# Schematic.net
KiCad netlist of a schematic drawn in Altium Designer
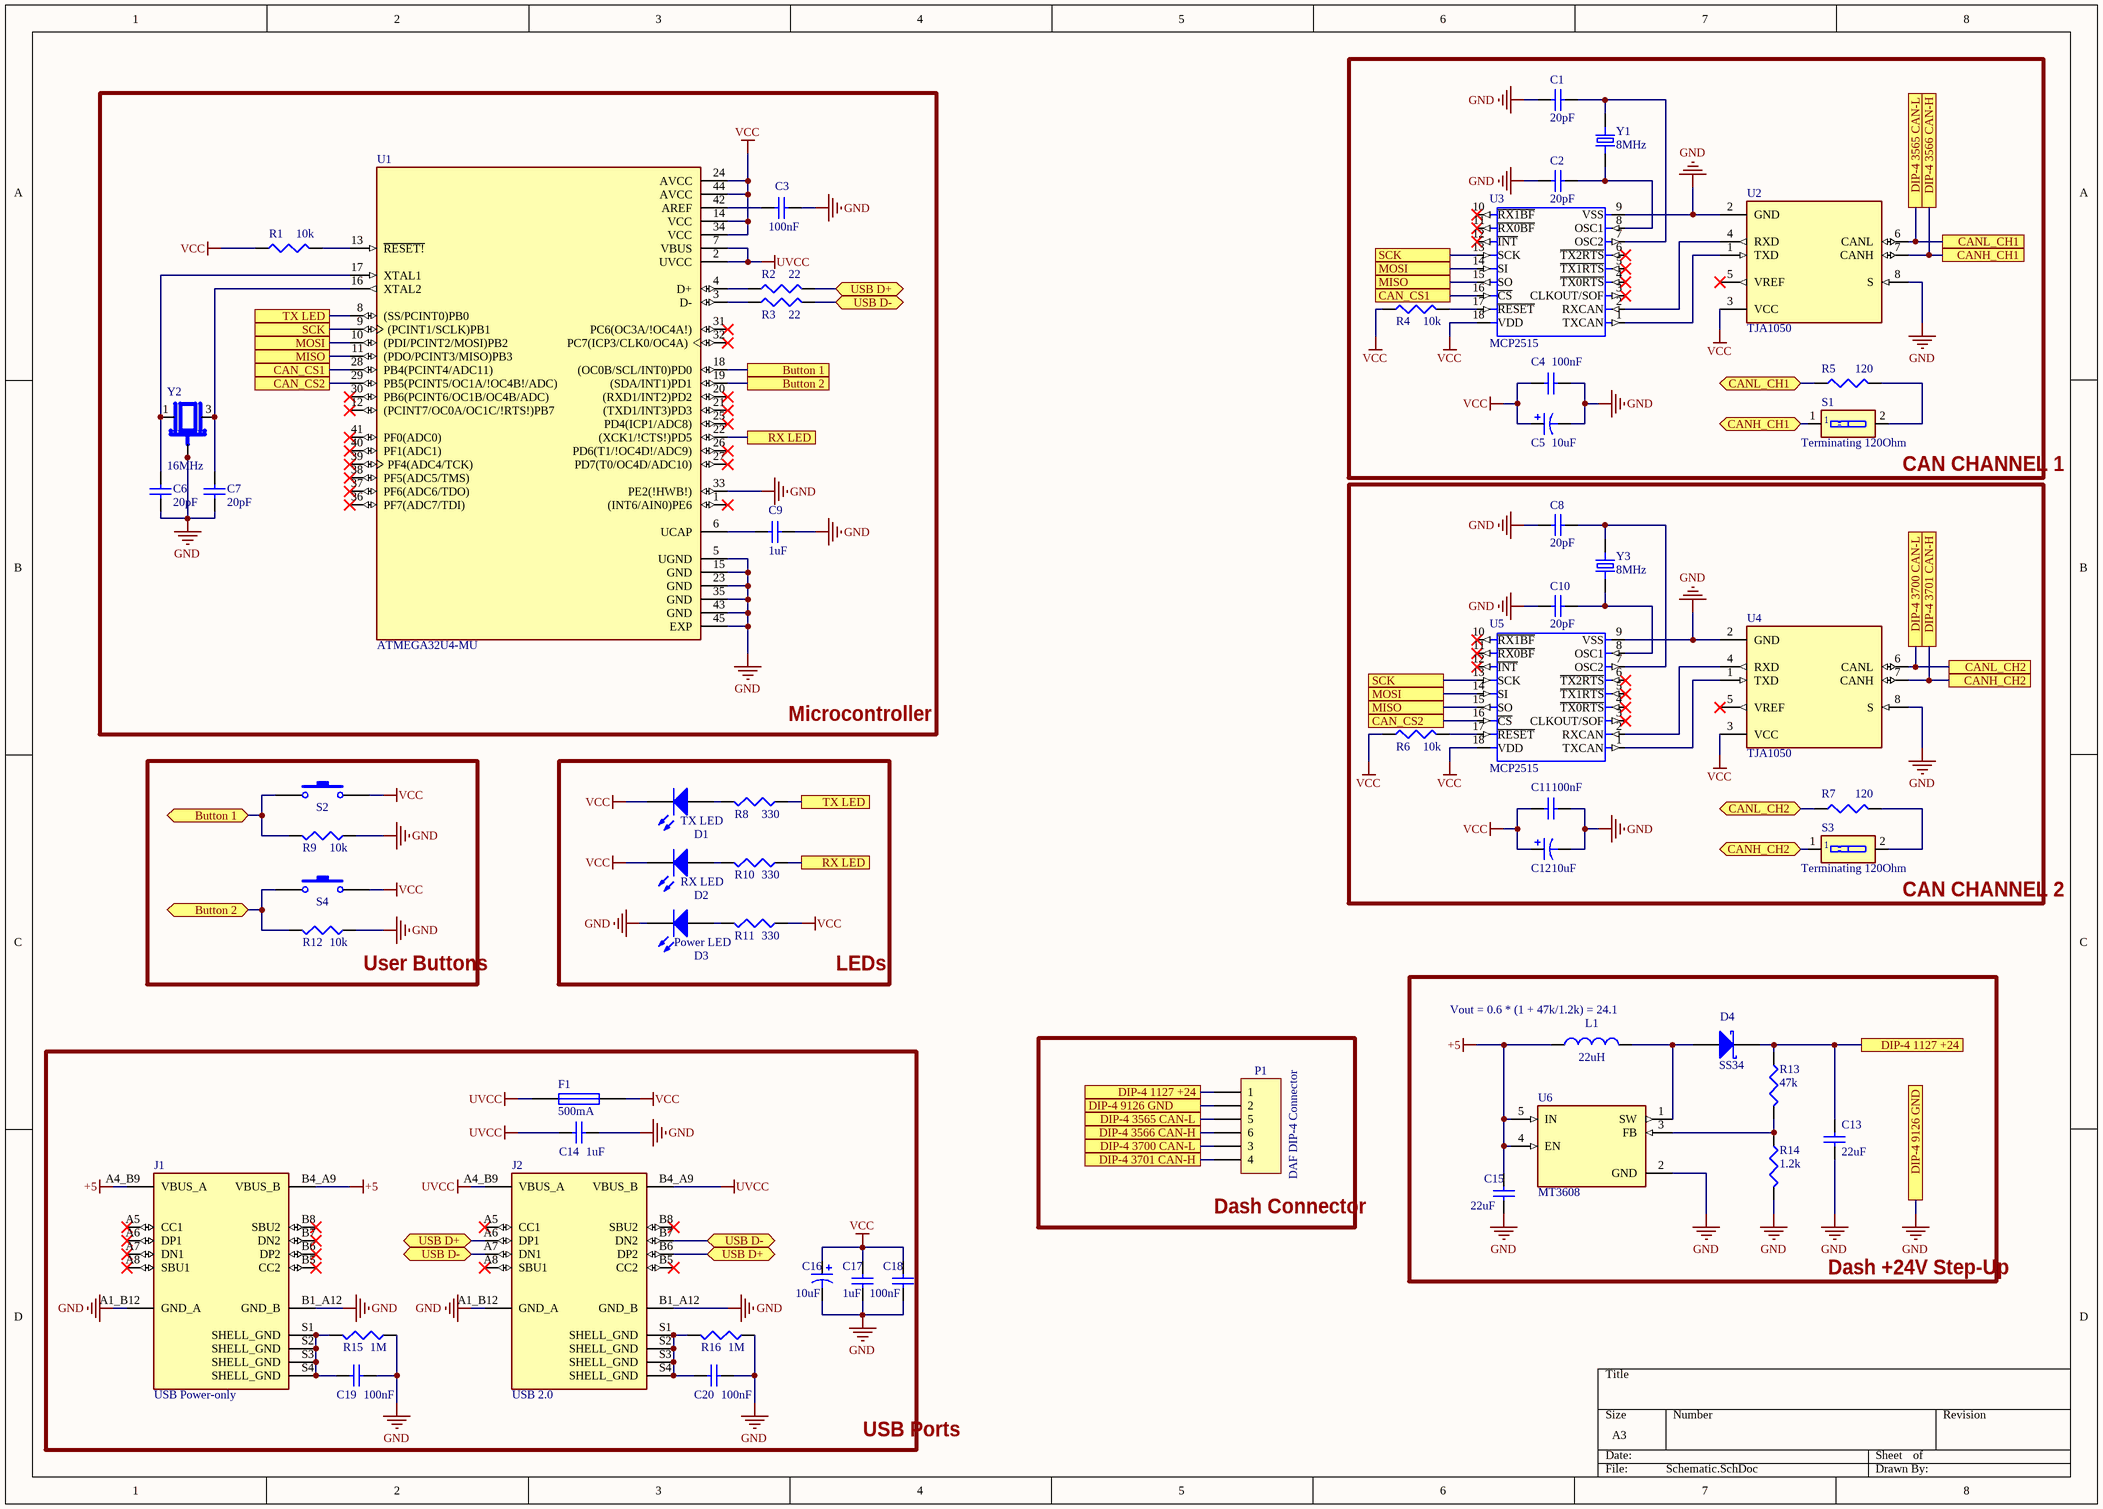
[diagram p0: Schematic.SchDoc]

(export (version "E")
  (design (tool "Eeschema 10.0.6"))
  (components
    (comp (ref "C1")
      (value "20pF")
      (footprint "C0805")
      (description "Capacitor")
      (fields (field (name "Comment") "Cap") (field (name "PUBLISHER") "Altium Limited"))
      (libsource (lib "Miscellaneous Devices") (part "Cap"))
    )
    (comp (ref "C2")
      (value "20pF")
      (footprint "C0805")
      (description "Capacitor")
      (fields (field (name "Comment") "Cap") (field (name "PUBLISHER") "Altium Limited"))
      (libsource (lib "Miscellaneous Devices") (part "Cap"))
    )
    (comp (ref "C3")
      (value "100nF")
      (footprint "C0805")
      (description "Capacitor")
      (fields (field (name "Comment") "Cap") (field (name "PUBLISHER") "Altium Limited"))
      (libsource (lib "Miscellaneous Devices") (part "Cap"))
    )
    (comp (ref "C4")
      (value "100nF")
      (footprint "C0805")
      (description "Capacitor")
      (fields (field (name "Comment") "Cap") (field (name "PUBLISHER") "Altium Limited"))
      (libsource (lib "Miscellaneous Devices") (part "Cap"))
    )
    (comp (ref "C5")
      (value "10uF")
      (footprint "C1206")
      (description "Polarized Capacitor (Surface Mount)")
      (fields (field (name "Comment") "Cap Pol3") (field (name "PUBLISHER") "Altium Limited"))
      (libsource (lib "Miscellaneous Devices") (part "Cap Pol3"))
    )
    (comp (ref "C6")
      (value "20pF")
      (footprint "C0805")
      (description "Capacitor")
      (fields (field (name "Comment") "Cap") (field (name "PUBLISHER") "Altium Limited"))
      (libsource (lib "Miscellaneous Devices") (part "Cap"))
    )
    (comp (ref "C7")
      (value "20pF")
      (footprint "C0805")
      (description "Capacitor")
      (fields (field (name "Comment") "Cap") (field (name "PUBLISHER") "Altium Limited"))
      (libsource (lib "Miscellaneous Devices") (part "Cap"))
    )
    (comp (ref "C8")
      (value "20pF")
      (footprint "C0805")
      (description "Capacitor")
      (fields (field (name "Comment") "Cap") (field (name "PUBLISHER") "Altium Limited"))
      (libsource (lib "Miscellaneous Devices") (part "Cap"))
    )
    (comp (ref "C9")
      (value "1uF")
      (footprint "C0805")
      (description "Capacitor")
      (fields (field (name "Comment") "Cap") (field (name "PUBLISHER") "Altium Limited"))
      (libsource (lib "Miscellaneous Devices") (part "Cap"))
    )
    (comp (ref "C10")
      (value "20pF")
      (footprint "C0805")
      (description "Capacitor")
      (fields (field (name "Comment") "Cap") (field (name "PUBLISHER") "Altium Limited"))
      (libsource (lib "Miscellaneous Devices") (part "Cap"))
    )
    (comp (ref "C11")
      (value "100nF")
      (footprint "C0805")
      (description "Capacitor")
      (fields (field (name "Comment") "Cap") (field (name "PUBLISHER") "Altium Limited"))
      (libsource (lib "Miscellaneous Devices") (part "Cap"))
    )
    (comp (ref "C12")
      (value "10uF")
      (footprint "C1206")
      (description "Polarized Capacitor (Surface Mount)")
      (fields (field (name "Comment") "Cap Pol3") (field (name "PUBLISHER") "Altium Limited"))
      (libsource (lib "Miscellaneous Devices") (part "Cap Pol3"))
    )
    (comp (ref "C13")
      (value "22uF")
      (footprint "C1206")
      (description "Capacitor")
      (fields (field (name "Comment") "Cap") (field (name "PUBLISHER") "Altium Limited"))
      (libsource (lib "Miscellaneous Devices") (part "Cap"))
    )
    (comp (ref "C14")
      (value "1uF")
      (footprint "C0805")
      (description "Capacitor")
      (fields (field (name "Comment") "Cap") (field (name "PUBLISHER") "Altium Limited"))
      (libsource (lib "Miscellaneous Devices") (part "Cap"))
    )
    (comp (ref "C15")
      (value "22uF")
      (footprint "C1206")
      (description "Capacitor")
      (fields (field (name "Comment") "Cap") (field (name "PUBLISHER") "Altium Limited"))
      (libsource (lib "Miscellaneous Devices") (part "Cap"))
    )
    (comp (ref "C16")
      (value "10uF")
      (footprint "C1206")
      (description "Polarized Capacitor (Surface Mount)")
      (fields (field (name "Comment") "Cap Pol3") (field (name "PUBLISHER") "Altium Limited"))
      (libsource (lib "Miscellaneous Devices") (part "Cap Pol3"))
    )
    (comp (ref "C17")
      (value "1uF")
      (footprint "C0805")
      (description "Capacitor")
      (fields (field (name "Comment") "Cap") (field (name "PUBLISHER") "Altium Limited"))
      (libsource (lib "Miscellaneous Devices") (part "Cap"))
    )
    (comp (ref "C18")
      (value "100nF")
      (footprint "C0805")
      (description "Capacitor")
      (fields (field (name "Comment") "Cap") (field (name "PUBLISHER") "Altium Limited"))
      (libsource (lib "Miscellaneous Devices") (part "Cap"))
    )
    (comp (ref "C19")
      (value "100nF")
      (footprint "C0805")
      (description "Capacitor")
      (fields (field (name "Comment") "Cap") (field (name "PUBLISHER") "Altium Limited"))
      (libsource (lib "Miscellaneous Devices") (part "Cap"))
    )
    (comp (ref "C20")
      (value "100nF")
      (footprint "C0805")
      (description "Capacitor")
      (fields (field (name "Comment") "Cap") (field (name "PUBLISHER") "Altium Limited"))
      (libsource (lib "Miscellaneous Devices") (part "Cap"))
    )
    (comp (ref "D1")
      (value "TX LED")
      (footprint "6-0805_L")
      (description "Typical RED GaAs LED")
      (fields (field (name "PUBLISHER") "Altium Limited"))
      (libsource (lib "Miscellaneous Devices") (part "LED1"))
    )
    (comp (ref "D2")
      (value "RX LED")
      (footprint "6-0805_L")
      (description "Typical RED GaAs LED")
      (fields (field (name "PUBLISHER") "Altium Limited"))
      (libsource (lib "Miscellaneous Devices") (part "LED1"))
    )
    (comp (ref "D3")
      (value "Power LED")
      (footprint "6-0805_L")
      (description "Typical RED GaAs LED")
      (fields (field (name "PUBLISHER") "Altium Limited"))
      (libsource (lib "Miscellaneous Devices") (part "LED1"))
    )
    (comp (ref "D4")
      (value "SS34")
      (footprint "SMC")
      (description "Schottky Diode")
      (fields (field (name "PUBLISHER") "Altium Limited"))
      (libsource (lib "Miscellaneous Devices") (part "D Schottky"))
    )
    (comp (ref "F1")
      (value "500mA")
      (footprint "C1206")
      (description "Fuse")
      (fields (field (name "PUBLISHER") "Altium Limited"))
      (libsource (lib "Miscellaneous Devices") (part "Fuse 1"))
    )
    (comp (ref "J1")
      (value "USB Power-only")
      (footprint "GCT_USB4505-03-0-A_REVA")
      (fields (field (name "MP") "USB4505-03-0-A") (field (name "MF") "Global Connector Technology"))
      (libsource (lib "Type-c") (part "USB4505-03-0-A_REVA"))
    )
    (comp (ref "J2")
      (value "USB 2.0")
      (footprint "GCT_USB4505-03-0-A_REVA")
      (fields (field (name "MP") "USB4505-03-0-A") (field (name "MF") "Global Connector Technology"))
      (libsource (lib "Type-c") (part "USB4505-03-0-A_REVA"))
    )
    (comp (ref "L1")
      (value "22uH")
      (footprint "IND_#B966BS-220M=P3")
      (description "Inductor")
      (fields (field (name "PUBLISHER") "Altium Limited"))
      (libsource (lib "Miscellaneous Devices") (part "Inductor"))
    )
    (comp (ref "P1")
      (value "DAF DIP-4 Connector")
      (footprint "HDR1X6")
      (description "Header, 6-Pin")
      (fields (field (name "PUBLISHER") "Altium Limited"))
      (libsource (lib "Miscellaneous Connectors") (part "Header 6"))
    )
    (comp (ref "R1")
      (value "10k")
      (footprint "6-0805_L")
      (description "Resistor")
      (fields (field (name "Comment") "Res3") (field (name "PUBLISHER") "Altium Limited"))
      (libsource (lib "Miscellaneous Devices") (part "Res3"))
    )
    (comp (ref "R2")
      (value "22")
      (footprint "J1-0603")
      (description "Resistor")
      (fields (field (name "Comment") "Res3") (field (name "PUBLISHER") "Altium Limited"))
      (libsource (lib "Miscellaneous Devices") (part "Res3"))
    )
    (comp (ref "R3")
      (value "22")
      (footprint "J1-0603")
      (description "Resistor")
      (fields (field (name "Comment") "Res3") (field (name "PUBLISHER") "Altium Limited"))
      (libsource (lib "Miscellaneous Devices") (part "Res3"))
    )
    (comp (ref "R4")
      (value "10k")
      (footprint "6-0805_L")
      (description "Resistor")
      (fields (field (name "Comment") "Res3") (field (name "PUBLISHER") "Altium Limited"))
      (libsource (lib "Miscellaneous Devices") (part "Res3"))
    )
    (comp (ref "R5")
      (value "120")
      (footprint "6-0805_L")
      (description "Resistor")
      (fields (field (name "Comment") "Res3") (field (name "PUBLISHER") "Altium Limited"))
      (libsource (lib "Miscellaneous Devices") (part "Res3"))
    )
    (comp (ref "R6")
      (value "10k")
      (footprint "6-0805_L")
      (description "Resistor")
      (fields (field (name "Comment") "Res3") (field (name "PUBLISHER") "Altium Limited"))
      (libsource (lib "Miscellaneous Devices") (part "Res3"))
    )
    (comp (ref "R7")
      (value "120")
      (footprint "6-0805_L")
      (description "Resistor")
      (fields (field (name "Comment") "Res3") (field (name "PUBLISHER") "Altium Limited"))
      (libsource (lib "Miscellaneous Devices") (part "Res3"))
    )
    (comp (ref "R8")
      (value "330")
      (footprint "6-0805_L")
      (description "Resistor")
      (fields (field (name "Comment") "Res3") (field (name "PUBLISHER") "Altium Limited"))
      (libsource (lib "Miscellaneous Devices") (part "Res3"))
    )
    (comp (ref "R9")
      (value "10k")
      (footprint "6-0805_L")
      (description "Resistor")
      (fields (field (name "Comment") "Res3") (field (name "PUBLISHER") "Altium Limited"))
      (libsource (lib "Miscellaneous Devices") (part "Res3"))
    )
    (comp (ref "R10")
      (value "330")
      (footprint "6-0805_L")
      (description "Resistor")
      (fields (field (name "Comment") "Res3") (field (name "PUBLISHER") "Altium Limited"))
      (libsource (lib "Miscellaneous Devices") (part "Res3"))
    )
    (comp (ref "R11")
      (value "330")
      (footprint "6-0805_L")
      (description "Resistor")
      (fields (field (name "Comment") "Res3") (field (name "PUBLISHER") "Altium Limited"))
      (libsource (lib "Miscellaneous Devices") (part "Res3"))
    )
    (comp (ref "R12")
      (value "10k")
      (footprint "6-0805_L")
      (description "Resistor")
      (fields (field (name "Comment") "Res3") (field (name "PUBLISHER") "Altium Limited"))
      (libsource (lib "Miscellaneous Devices") (part "Res3"))
    )
    (comp (ref "R13")
      (value "47k")
      (footprint "6-0805_L")
      (description "Resistor")
      (fields (field (name "Comment") "Res3") (field (name "PUBLISHER") "Altium Limited"))
      (libsource (lib "Miscellaneous Devices") (part "Res3"))
    )
    (comp (ref "R14")
      (value "1.2k")
      (footprint "6-0805_L")
      (description "Resistor")
      (fields (field (name "Comment") "Res3") (field (name "PUBLISHER") "Altium Limited"))
      (libsource (lib "Miscellaneous Devices") (part "Res3"))
    )
    (comp (ref "R15")
      (value "1M")
      (footprint "6-0805_L")
      (description "Resistor")
      (fields (field (name "Comment") "Res3") (field (name "PUBLISHER") "Altium Limited"))
      (libsource (lib "Miscellaneous Devices") (part "Res3"))
    )
    (comp (ref "R16")
      (value "1M")
      (footprint "6-0805_L")
      (description "Resistor")
      (fields (field (name "Comment") "Res3") (field (name "PUBLISHER") "Altium Limited"))
      (libsource (lib "Miscellaneous Devices") (part "Res3"))
    )
    (comp (ref "S1")
      (value "Terminating 120Ohm")
      (footprint "SW_5161390-1")
      (description "Switch DIP OFF ON SPST 1 Top Slide 25A 50VDC PC Pins 2.54mm Thru-Hole Box/Carton")
      (fields (field (name "MP") "5161390-1") (field (name "MF") "TE Connectivity"))
      (libsource (lib "DIP 1 switch") (part "5161390-1"))
    )
    (comp (ref "S2")
      (value "SW-PB")
      (footprint "SW_147873-2")
      (description "Switch")
      (fields (field (name "PUBLISHER") "Altium Limited"))
      (libsource (lib "Miscellaneous Devices") (part "SW-PB"))
    )
    (comp (ref "S3")
      (value "Terminating 120Ohm")
      (footprint "SW_5161390-1")
      (description "Switch DIP OFF ON SPST 1 Top Slide 25A 50VDC PC Pins 2.54mm Thru-Hole Box/Carton")
      (fields (field (name "MP") "5161390-1") (field (name "MF") "TE Connectivity"))
      (libsource (lib "DIP 1 switch") (part "5161390-1"))
    )
    (comp (ref "S4")
      (value "SW-PB")
      (footprint "SW_147873-2")
      (description "Switch")
      (fields (field (name "PUBLISHER") "Altium Limited"))
      (libsource (lib "Miscellaneous Devices") (part "SW-PB"))
    )
    (comp (ref "U1")
      (value "ATMEGA32U4-MU")
      (footprint "QFN50P700X700X100-45N")
      (description "AVR AVRÂ® ATmega Microcontroller IC 8-Bit 16MHz 32KB (16K x 16) FLASH 44-VQFN (7x7)")
      (fields (field (name "MF") "Microchip Technology / Atmel"))
      (libsource (lib "ATMEGA32U4-MU") (part "ATMEGA32U4-MU"))
    )
    (comp (ref "U2")
      (value "TJA1050")
      (footprint "SOIC127P600X175-8N")
      (description "1/1 Transceiver Half CANbus 8-SO")
      (fields (field (name "MF") "NXP USA") (field (name "MP") "TJA1050T/CM,118"))
      (libsource (lib "TJA1050T_CM_118") (part "TJA1050T/CM,118"))
    )
    (comp (ref "U3")
      (value "MCP2515")
      (footprint "SOIC18-1.27-11.5X7.5MM")
      (description "IC CAN CONTROLLER W/SPI 18SOIC")
      (fields (field (name "MF") "Microchip Technology") (field (name "MP") "MCP2515T-I/SO"))
      (libsource (lib "INTERFACE-MCP2515T-I_SO_SOIC18_") (part "INTERFACE-MCP2515T-I/SO(SOIC18)"))
    )
    (comp (ref "U4")
      (value "TJA1050")
      (footprint "SOIC127P600X175-8N")
      (description "1/1 Transceiver Half CANbus 8-SO")
      (fields (field (name "MF") "NXP USA") (field (name "MP") "TJA1050T/CM,118"))
      (libsource (lib "TJA1050T_CM_118") (part "TJA1050T/CM,118"))
    )
    (comp (ref "U5")
      (value "MCP2515")
      (footprint "SOIC18-1.27-11.5X7.5MM")
      (description "IC CAN CONTROLLER W/SPI 18SOIC")
      (fields (field (name "MF") "Microchip Technology") (field (name "MP") "MCP2515T-I/SO"))
      (libsource (lib "INTERFACE-MCP2515T-I_SO_SOIC18_") (part "INTERFACE-MCP2515T-I/SO(SOIC18)"))
    )
    (comp (ref "U6")
      (value "MT3608")
      (footprint "SOT95P280X145-6N")
      (description "High Efficiency 1.2MHz2A Step Up Converter")
      (fields (field (name "MF") "Aerosemi Technology Co., Ltd"))
      (libsource (lib "MT3608") (part "MT3608"))
    )
    (comp (ref "Y1")
      (value "8MHz")
      (footprint "XTAL_ECS-135-S-1")
      (fields (field (name "MP") "ECS-135-S-1"))
      (libsource (lib "quartz TH") (part "ECS-135-S-1"))
    )
    (comp (ref "Y2")
      (value "16MHz")
      (footprint "OSC_ABM3B-16.000MHZ-D-1-X-T")
      (description "16 MHz Â±10ppm Crystal 18pF 50 Ohms 4-SMD, No Lead")
      (fields (field (name "MP") "ABM3B-16.000MHZ-D-1-X-T") (field (name "MF") "ABRACON"))
      (libsource (lib "quartz") (part "ABM3B-16.000MHZ-D-1-X-T"))
    )
    (comp (ref "Y3")
      (value "8MHz")
      (footprint "XTAL_ECS-135-S-1")
      (fields (field (name "MP") "ECS-135-S-1"))
      (libsource (lib "quartz TH") (part "ECS-135-S-1"))
    )
  )
  (nets
    (net (code "1") (name "+5") (class "Default")
      (node (ref "C15") (pin "2") (pinfunction "2_2") (pintype "passive"))
      (node (ref "J1") (pin "A4_B9") (pinfunction "VBUS_A_A4_B9") (pintype "power_in"))
      (node (ref "J1") (pin "B4_A9") (pinfunction "VBUS_B_B4_A9") (pintype "power_in"))
      (node (ref "L1") (pin "1") (pinfunction "1_1") (pintype "passive"))
      (node (ref "U6") (pin "4") (pinfunction "EN_4") (pintype "input"))
      (node (ref "U6") (pin "5") (pinfunction "IN_5") (pintype "input"))
    )
    (net (code "2") (name "/Button 1") (class "Default")
      (node (ref "R9") (pin "2") (pinfunction "2_2") (pintype "passive"))
      (node (ref "S2") (pin "1") (pinfunction "1_1") (pintype "passive"))
      (node (ref "U1") (pin "18") (pinfunction "(OC0B/SCL/INT0)PD0_18") (pintype "bidirectional"))
    )
    (net (code "3") (name "/Button 2") (class "Default")
      (node (ref "R12") (pin "2") (pinfunction "2_2") (pintype "passive"))
      (node (ref "S4") (pin "1") (pinfunction "1_1") (pintype "passive"))
      (node (ref "U1") (pin "19") (pinfunction "(SDA/INT1)PD1_19") (pintype "bidirectional"))
    )
    (net (code "4") (name "/CANH_CH1") (class "Default")
      (node (ref "P1") (pin "6") (pinfunction "6_6") (pintype "passive"))
      (node (ref "S1") (pin "1") (pinfunction "1_1") (pintype "passive"))
      (node (ref "U2") (pin "7") (pinfunction "CANH_7") (pintype "bidirectional"))
    )
    (net (code "5") (name "/CANH_CH2") (class "Default")
      (node (ref "P1") (pin "4") (pinfunction "4_4") (pintype "passive"))
      (node (ref "S3") (pin "1") (pinfunction "1_1") (pintype "passive"))
      (node (ref "U4") (pin "7") (pinfunction "CANH_7") (pintype "bidirectional"))
    )
    (net (code "6") (name "/CANL_CH1") (class "Default")
      (node (ref "P1") (pin "5") (pinfunction "5_5") (pintype "passive"))
      (node (ref "R5") (pin "1") (pinfunction "1_1") (pintype "passive"))
      (node (ref "U2") (pin "6") (pinfunction "CANL_6") (pintype "bidirectional"))
    )
    (net (code "7") (name "/CANL_CH2") (class "Default")
      (node (ref "P1") (pin "3") (pinfunction "3_3") (pintype "passive"))
      (node (ref "R7") (pin "1") (pinfunction "1_1") (pintype "passive"))
      (node (ref "U4") (pin "6") (pinfunction "CANL_6") (pintype "bidirectional"))
    )
    (net (code "8") (name "/CAN_CS1") (class "Default")
      (node (ref "U1") (pin "28") (pinfunction "PB4(PCINT4/ADC11)_28") (pintype "bidirectional"))
      (node (ref "U3") (pin "16") (pinfunction "~{CS}_16") (pintype "input"))
    )
    (net (code "9") (name "/CAN_CS2") (class "Default")
      (node (ref "U1") (pin "29") (pinfunction "PB5(PCINT5/OC1A/!OC4B!/ADC)_29") (pintype "bidirectional"))
      (node (ref "U5") (pin "16") (pinfunction "~{CS}_16") (pintype "input"))
    )
    (net (code "10") (name "/DIP-4 1127 +24") (class "Default")
      (node (ref "C13") (pin "2") (pinfunction "2_2") (pintype "passive"))
      (node (ref "D4") (pin "2") (pinfunction "K_2") (pintype "passive"))
      (node (ref "P1") (pin "1") (pinfunction "1_1") (pintype "passive"))
      (node (ref "R13") (pin "1") (pinfunction "1_1") (pintype "passive"))
    )
    (net (code "11") (name "/MISO") (class "Default")
      (node (ref "U1") (pin "11") (pinfunction "(PDO/PCINT3/MISO)PB3_11") (pintype "bidirectional"))
      (node (ref "U3") (pin "15") (pinfunction "SO_15") (pintype "output"))
      (node (ref "U5") (pin "15") (pinfunction "SO_15") (pintype "output"))
    )
    (net (code "12") (name "/MOSI") (class "Default")
      (node (ref "U1") (pin "10") (pinfunction "(PDI/PCINT2/MOSI)PB2_10") (pintype "bidirectional"))
      (node (ref "U3") (pin "14") (pinfunction "SI_14") (pintype "input"))
      (node (ref "U5") (pin "14") (pinfunction "SI_14") (pintype "input"))
    )
    (net (code "13") (name "/RX LED") (class "Default")
      (node (ref "R10") (pin "1") (pinfunction "1_1") (pintype "passive"))
      (node (ref "U1") (pin "22") (pinfunction "(XCK1/!CTS!)PD5_22") (pintype "bidirectional"))
    )
    (net (code "14") (name "/SCK") (class "Default")
      (node (ref "U1") (pin "9") (pinfunction "(PCINT1/SCLK)PB1_9") (pintype "bidirectional"))
      (node (ref "U3") (pin "13") (pinfunction "SCK_13") (pintype "input"))
      (node (ref "U5") (pin "13") (pinfunction "SCK_13") (pintype "input"))
    )
    (net (code "15") (name "/TX LED") (class "Default")
      (node (ref "R8") (pin "1") (pinfunction "1_1") (pintype "passive"))
      (node (ref "U1") (pin "8") (pinfunction "(SS/PCINT0)PB0_8") (pintype "bidirectional"))
    )
    (net (code "16") (name "/USB D+") (class "Default")
      (node (ref "J2") (pin "A6") (pinfunction "DP1_A6") (pintype "bidirectional"))
      (node (ref "J2") (pin "B6") (pinfunction "DP2_B6") (pintype "bidirectional"))
      (node (ref "R2") (pin "2") (pinfunction "2_2") (pintype "passive"))
    )
    (net (code "17") (name "/USB D-") (class "Default")
      (node (ref "J2") (pin "A7") (pinfunction "DN1_A7") (pintype "bidirectional"))
      (node (ref "J2") (pin "B7") (pinfunction "DN2_B7") (pintype "bidirectional"))
      (node (ref "R3") (pin "2") (pinfunction "2_2") (pintype "passive"))
    )
    (net (code "18") (name "GND") (class "Default")
      (node (ref "C1") (pin "1") (pinfunction "1_1") (pintype "passive"))
      (node (ref "C10") (pin "1") (pinfunction "1_1") (pintype "passive"))
      (node (ref "C11") (pin "2") (pinfunction "2_2") (pintype "passive"))
      (node (ref "C12") (pin "2") (pinfunction "2_2") (pintype "passive"))
      (node (ref "C13") (pin "1") (pinfunction "1_1") (pintype "passive"))
      (node (ref "C14") (pin "1") (pinfunction "1_1") (pintype "passive"))
      (node (ref "C15") (pin "1") (pinfunction "1_1") (pintype "passive"))
      (node (ref "C16") (pin "2") (pinfunction "2_2") (pintype "passive"))
      (node (ref "C17") (pin "1") (pinfunction "1_1") (pintype "passive"))
      (node (ref "C18") (pin "1") (pinfunction "1_1") (pintype "passive"))
      (node (ref "C19") (pin "2") (pinfunction "2_2") (pintype "passive"))
      (node (ref "C2") (pin "1") (pinfunction "1_1") (pintype "passive"))
      (node (ref "C20") (pin "2") (pinfunction "2_2") (pintype "passive"))
      (node (ref "C3") (pin "1") (pinfunction "1_1") (pintype "passive"))
      (node (ref "C4") (pin "2") (pinfunction "2_2") (pintype "passive"))
      (node (ref "C5") (pin "2") (pinfunction "2_2") (pintype "passive"))
      (node (ref "C6") (pin "1") (pinfunction "1_1") (pintype "passive"))
      (node (ref "C7") (pin "1") (pinfunction "1_1") (pintype "passive"))
      (node (ref "C8") (pin "1") (pinfunction "1_1") (pintype "passive"))
      (node (ref "C9") (pin "1") (pinfunction "1_1") (pintype "passive"))
      (node (ref "D3") (pin "2") (pinfunction "K_2") (pintype "passive"))
      (node (ref "J1") (pin "A1_B12") (pinfunction "GND_A_A1_B12") (pintype "power_in"))
      (node (ref "J1") (pin "B1_A12") (pinfunction "GND_B_B1_A12") (pintype "power_in"))
      (node (ref "J2") (pin "A1_B12") (pinfunction "GND_A_A1_B12") (pintype "power_in"))
      (node (ref "J2") (pin "B1_A12") (pinfunction "GND_B_B1_A12") (pintype "power_in"))
      (node (ref "P1") (pin "2") (pinfunction "2_2") (pintype "passive"))
      (node (ref "R12") (pin "1") (pinfunction "1_1") (pintype "passive"))
      (node (ref "R14") (pin "2") (pinfunction "2_2") (pintype "passive"))
      (node (ref "R15") (pin "1") (pinfunction "1_1") (pintype "passive"))
      (node (ref "R16") (pin "1") (pinfunction "1_1") (pintype "passive"))
      (node (ref "R9") (pin "1") (pinfunction "1_1") (pintype "passive"))
      (node (ref "U1") (pin "15") (pinfunction "GND_15") (pintype "power_in"))
      (node (ref "U1") (pin "23") (pinfunction "GND_23") (pintype "power_in"))
      (node (ref "U1") (pin "33") (pinfunction "PE2(!HWB!)_33") (pintype "bidirectional"))
      (node (ref "U1") (pin "35") (pinfunction "GND_35") (pintype "power_in"))
      (node (ref "U1") (pin "43") (pinfunction "GND_43") (pintype "power_in"))
      (node (ref "U1") (pin "45") (pinfunction "EXP_45") (pintype "passive"))
      (node (ref "U1") (pin "5") (pinfunction "UGND_5") (pintype "power_in"))
      (node (ref "U2") (pin "2") (pinfunction "GND_2") (pintype "power_in"))
      (node (ref "U2") (pin "8") (pinfunction "S_8") (pintype "input"))
      (node (ref "U3") (pin "9") (pinfunction "VSS_9") (pintype "power_in"))
      (node (ref "U4") (pin "2") (pinfunction "GND_2") (pintype "power_in"))
      (node (ref "U4") (pin "8") (pinfunction "S_8") (pintype "input"))
      (node (ref "U5") (pin "9") (pinfunction "VSS_9") (pintype "power_in"))
      (node (ref "U6") (pin "2") (pinfunction "GND_2") (pintype "power_in"))
      (node (ref "Y2") (pin "2") (pinfunction "GND_2") (pintype "power_in"))
      (node (ref "Y2") (pin "4") (pinfunction "GND_4") (pintype "power_in"))
    )
    (net (code "19") (name "Net-(C19-Pad1)") (class "Default")
      (node (ref "C19") (pin "1") (pinfunction "1_1") (pintype "passive"))
      (node (ref "J1") (pin "S1") (pinfunction "SHELL_GND_S1") (pintype "power_in"))
      (node (ref "J1") (pin "S2") (pinfunction "SHELL_GND_S2") (pintype "power_in"))
      (node (ref "J1") (pin "S3") (pinfunction "SHELL_GND_S3") (pintype "power_in"))
      (node (ref "J1") (pin "S4") (pinfunction "SHELL_GND_S4") (pintype "power_in"))
      (node (ref "R15") (pin "2") (pinfunction "2_2") (pintype "passive"))
    )
    (net (code "20") (name "Net-(C20-Pad1)") (class "Default")
      (node (ref "C20") (pin "1") (pinfunction "1_1") (pintype "passive"))
      (node (ref "J2") (pin "S1") (pinfunction "SHELL_GND_S1") (pintype "power_in"))
      (node (ref "J2") (pin "S2") (pinfunction "SHELL_GND_S2") (pintype "power_in"))
      (node (ref "J2") (pin "S3") (pinfunction "SHELL_GND_S3") (pintype "power_in"))
      (node (ref "J2") (pin "S4") (pinfunction "SHELL_GND_S4") (pintype "power_in"))
      (node (ref "R16") (pin "2") (pinfunction "2_2") (pintype "passive"))
    )
    (net (code "21") (name "Net-(D1-A)") (class "Default")
      (node (ref "D1") (pin "1") (pinfunction "A_1") (pintype "passive"))
      (node (ref "R8") (pin "2") (pinfunction "2_2") (pintype "passive"))
    )
    (net (code "22") (name "Net-(D2-A)") (class "Default")
      (node (ref "D2") (pin "1") (pinfunction "A_1") (pintype "passive"))
      (node (ref "R10") (pin "2") (pinfunction "2_2") (pintype "passive"))
    )
    (net (code "23") (name "Net-(D3-A)") (class "Default")
      (node (ref "D3") (pin "1") (pinfunction "A_1") (pintype "passive"))
      (node (ref "R11") (pin "2") (pinfunction "2_2") (pintype "passive"))
    )
    (net (code "24") (name "Net-(D4-A)") (class "Default")
      (node (ref "D4") (pin "1") (pinfunction "A_1") (pintype "passive"))
      (node (ref "L1") (pin "2") (pinfunction "2_2") (pintype "passive"))
      (node (ref "U6") (pin "1") (pinfunction "SW_1") (pintype "output"))
    )
    (net (code "25") (name "Net-(R5-Pad2)") (class "Default")
      (node (ref "R5") (pin "2") (pinfunction "2_2") (pintype "passive"))
      (node (ref "S1") (pin "2") (pinfunction "2_2") (pintype "passive"))
    )
    (net (code "26") (name "Net-(R7-Pad2)") (class "Default")
      (node (ref "R7") (pin "2") (pinfunction "2_2") (pintype "passive"))
      (node (ref "S3") (pin "2") (pinfunction "2_2") (pintype "passive"))
    )
    (net (code "27") (name "Net-(U1-AREF)") (class "Default")
      (node (ref "C3") (pin "2") (pinfunction "2_2") (pintype "passive"))
      (node (ref "U1") (pin "42") (pinfunction "AREF_42") (pintype "power_in"))
    )
    (net (code "28") (name "Net-(U1-D+)") (class "Default")
      (node (ref "R2") (pin "1") (pinfunction "1_1") (pintype "passive"))
      (node (ref "U1") (pin "4") (pinfunction "D+_4") (pintype "bidirectional"))
    )
    (net (code "29") (name "Net-(U1-D-)") (class "Default")
      (node (ref "R3") (pin "1") (pinfunction "1_1") (pintype "passive"))
      (node (ref "U1") (pin "3") (pinfunction "D-_3") (pintype "bidirectional"))
    )
    (net (code "30") (name "Net-(U1-UCAP)") (class "Default")
      (node (ref "C9") (pin "2") (pinfunction "2_2") (pintype "passive"))
      (node (ref "U1") (pin "6") (pinfunction "UCAP_6") (pintype "passive"))
    )
    (net (code "31") (name "Net-(U1-XTAL1)") (class "Default")
      (node (ref "C6") (pin "2") (pinfunction "2_2") (pintype "passive"))
      (node (ref "U1") (pin "17") (pinfunction "XTAL1_17") (pintype "input"))
      (node (ref "Y2") (pin "1") (pinfunction "1_1") (pintype "passive"))
    )
    (net (code "32") (name "Net-(U1-XTAL2)") (class "Default")
      (node (ref "C7") (pin "2") (pinfunction "2_2") (pintype "passive"))
      (node (ref "U1") (pin "16") (pinfunction "XTAL2_16") (pintype "output"))
      (node (ref "Y2") (pin "3") (pinfunction "3_3") (pintype "passive"))
    )
    (net (code "33") (name "Net-(U1-~{RESET!})") (class "Default")
      (node (ref "R1") (pin "2") (pinfunction "2_2") (pintype "passive"))
      (node (ref "U1") (pin "13") (pinfunction "~{RESET!}_13") (pintype "input"))
    )
    (net (code "34") (name "Net-(U2-RXD)") (class "Default")
      (node (ref "U2") (pin "4") (pinfunction "RXD_4") (pintype "output"))
      (node (ref "U3") (pin "2") (pinfunction "RXCAN_2") (pintype "input"))
    )
    (net (code "35") (name "Net-(U2-TXD)") (class "Default")
      (node (ref "U2") (pin "1") (pinfunction "TXD_1") (pintype "input"))
      (node (ref "U3") (pin "1") (pinfunction "TXCAN_1") (pintype "output"))
    )
    (net (code "36") (name "Net-(U3-OSC1)") (class "Default")
      (node (ref "C2") (pin "2") (pinfunction "2_2") (pintype "passive"))
      (node (ref "U3") (pin "8") (pinfunction "OSC1_8") (pintype "input"))
      (node (ref "Y1") (pin "2") (pinfunction "2_2") (pintype "passive"))
    )
    (net (code "37") (name "Net-(U3-OSC2)") (class "Default")
      (node (ref "C1") (pin "2") (pinfunction "2_2") (pintype "passive"))
      (node (ref "U3") (pin "7") (pinfunction "OSC2_7") (pintype "output"))
      (node (ref "Y1") (pin "1") (pinfunction "1_1") (pintype "passive"))
    )
    (net (code "38") (name "Net-(U3-~{RESET})") (class "Default")
      (node (ref "R4") (pin "2") (pinfunction "2_2") (pintype "passive"))
      (node (ref "U3") (pin "17") (pinfunction "~{RESET}_17") (pintype "input"))
    )
    (net (code "39") (name "Net-(U4-RXD)") (class "Default")
      (node (ref "U4") (pin "4") (pinfunction "RXD_4") (pintype "output"))
      (node (ref "U5") (pin "2") (pinfunction "RXCAN_2") (pintype "input"))
    )
    (net (code "40") (name "Net-(U4-TXD)") (class "Default")
      (node (ref "U4") (pin "1") (pinfunction "TXD_1") (pintype "input"))
      (node (ref "U5") (pin "1") (pinfunction "TXCAN_1") (pintype "output"))
    )
    (net (code "41") (name "Net-(U5-OSC1)") (class "Default")
      (node (ref "C10") (pin "2") (pinfunction "2_2") (pintype "passive"))
      (node (ref "U5") (pin "8") (pinfunction "OSC1_8") (pintype "input"))
      (node (ref "Y3") (pin "2") (pinfunction "2_2") (pintype "passive"))
    )
    (net (code "42") (name "Net-(U5-OSC2)") (class "Default")
      (node (ref "C8") (pin "2") (pinfunction "2_2") (pintype "passive"))
      (node (ref "U5") (pin "7") (pinfunction "OSC2_7") (pintype "output"))
      (node (ref "Y3") (pin "1") (pinfunction "1_1") (pintype "passive"))
    )
    (net (code "43") (name "Net-(U5-~{RESET})") (class "Default")
      (node (ref "R6") (pin "2") (pinfunction "2_2") (pintype "passive"))
      (node (ref "U5") (pin "17") (pinfunction "~{RESET}_17") (pintype "input"))
    )
    (net (code "44") (name "Net-(U6-FB)") (class "Default")
      (node (ref "R13") (pin "2") (pinfunction "2_2") (pintype "passive"))
      (node (ref "R14") (pin "1") (pinfunction "1_1") (pintype "passive"))
      (node (ref "U6") (pin "3") (pinfunction "FB_3") (pintype "input"))
    )
    (net (code "45") (name "UVCC") (class "Default")
      (node (ref "C14") (pin "2") (pinfunction "2_2") (pintype "passive"))
      (node (ref "F1") (pin "1") (pinfunction "1_1") (pintype "passive"))
      (node (ref "J2") (pin "A4_B9") (pinfunction "VBUS_A_A4_B9") (pintype "power_in"))
      (node (ref "J2") (pin "B4_A9") (pinfunction "VBUS_B_B4_A9") (pintype "power_in"))
      (node (ref "U1") (pin "2") (pinfunction "UVCC_2") (pintype "power_in"))
      (node (ref "U1") (pin "7") (pinfunction "VBUS_7") (pintype "power_in"))
    )
    (net (code "46") (name "VCC") (class "Default")
      (node (ref "C11") (pin "1") (pinfunction "1_1") (pintype "passive"))
      (node (ref "C12") (pin "1") (pinfunction "1_1") (pintype "passive"))
      (node (ref "C16") (pin "1") (pinfunction "1_1") (pintype "passive"))
      (node (ref "C17") (pin "2") (pinfunction "2_2") (pintype "passive"))
      (node (ref "C18") (pin "2") (pinfunction "2_2") (pintype "passive"))
      (node (ref "C4") (pin "1") (pinfunction "1_1") (pintype "passive"))
      (node (ref "C5") (pin "1") (pinfunction "1_1") (pintype "passive"))
      (node (ref "D1") (pin "2") (pinfunction "K_2") (pintype "passive"))
      (node (ref "D2") (pin "2") (pinfunction "K_2") (pintype "passive"))
      (node (ref "F1") (pin "2") (pinfunction "2_2") (pintype "passive"))
      (node (ref "R1") (pin "1") (pinfunction "1_1") (pintype "passive"))
      (node (ref "R11") (pin "1") (pinfunction "1_1") (pintype "passive"))
      (node (ref "R4") (pin "1") (pinfunction "1_1") (pintype "passive"))
      (node (ref "R6") (pin "1") (pinfunction "1_1") (pintype "passive"))
      (node (ref "S2") (pin "2") (pinfunction "2_2") (pintype "passive"))
      (node (ref "S4") (pin "2") (pinfunction "2_2") (pintype "passive"))
      (node (ref "U1") (pin "14") (pinfunction "VCC_14") (pintype "power_in"))
      (node (ref "U1") (pin "24") (pinfunction "AVCC_24") (pintype "power_in"))
      (node (ref "U1") (pin "34") (pinfunction "VCC_34") (pintype "power_in"))
      (node (ref "U1") (pin "44") (pinfunction "AVCC_44") (pintype "power_in"))
      (node (ref "U2") (pin "3") (pinfunction "VCC_3") (pintype "power_in"))
      (node (ref "U3") (pin "18") (pinfunction "VDD_18") (pintype "power_in"))
      (node (ref "U4") (pin "3") (pinfunction "VCC_3") (pintype "power_in"))
      (node (ref "U5") (pin "18") (pinfunction "VDD_18") (pintype "power_in"))
    )
    (net (code "47") (name "unconnected-(J1-CC1-PadA5)") (class "Default")
      (node (ref "J1") (pin "A5") (pinfunction "CC1_A5") (pintype "bidirectional+no_connect"))
    )
    (net (code "48") (name "unconnected-(J1-CC2-PadB5)") (class "Default")
      (node (ref "J1") (pin "B5") (pinfunction "CC2_B5") (pintype "bidirectional+no_connect"))
    )
    (net (code "49") (name "unconnected-(J1-DN1-PadA7)") (class "Default")
      (node (ref "J1") (pin "A7") (pinfunction "DN1_A7") (pintype "bidirectional+no_connect"))
    )
    (net (code "50") (name "unconnected-(J1-DN2-PadB7)") (class "Default")
      (node (ref "J1") (pin "B7") (pinfunction "DN2_B7") (pintype "bidirectional+no_connect"))
    )
    (net (code "51") (name "unconnected-(J1-DP1-PadA6)") (class "Default")
      (node (ref "J1") (pin "A6") (pinfunction "DP1_A6") (pintype "bidirectional+no_connect"))
    )
    (net (code "52") (name "unconnected-(J1-DP2-PadB6)") (class "Default")
      (node (ref "J1") (pin "B6") (pinfunction "DP2_B6") (pintype "bidirectional+no_connect"))
    )
    (net (code "53") (name "unconnected-(J1-SBU1-PadA8)") (class "Default")
      (node (ref "J1") (pin "A8") (pinfunction "SBU1_A8") (pintype "bidirectional+no_connect"))
    )
    (net (code "54") (name "unconnected-(J1-SBU2-PadB8)") (class "Default")
      (node (ref "J1") (pin "B8") (pinfunction "SBU2_B8") (pintype "bidirectional+no_connect"))
    )
    (net (code "55") (name "unconnected-(J2-CC1-PadA5)") (class "Default")
      (node (ref "J2") (pin "A5") (pinfunction "CC1_A5") (pintype "bidirectional+no_connect"))
    )
    (net (code "56") (name "unconnected-(J2-CC2-PadB5)") (class "Default")
      (node (ref "J2") (pin "B5") (pinfunction "CC2_B5") (pintype "bidirectional+no_connect"))
    )
    (net (code "57") (name "unconnected-(J2-SBU1-PadA8)") (class "Default")
      (node (ref "J2") (pin "A8") (pinfunction "SBU1_A8") (pintype "bidirectional+no_connect"))
    )
    (net (code "58") (name "unconnected-(J2-SBU2-PadB8)") (class "Default")
      (node (ref "J2") (pin "B8") (pinfunction "SBU2_B8") (pintype "bidirectional+no_connect"))
    )
    (net (code "59") (name "unconnected-(U1-(INT6{slash}AIN0)PE6-Pad1)") (class "Default")
      (node (ref "U1") (pin "1") (pinfunction "(INT6/AIN0)PE6_1") (pintype "bidirectional+no_connect"))
    )
    (net (code "60") (name "unconnected-(U1-(PCINT7{slash}OC0A{slash}OC1C{slash}!RTS!)PB7-Pad12)") (class "Default")
      (node (ref "U1") (pin "12") (pinfunction "(PCINT7/OC0A/OC1C/!RTS!)PB7_12") (pintype "bidirectional+no_connect"))
    )
    (net (code "61") (name "unconnected-(U1-(RXD1{slash}INT2)PD2-Pad20)") (class "Default")
      (node (ref "U1") (pin "20") (pinfunction "(RXD1/INT2)PD2_20") (pintype "bidirectional+no_connect"))
    )
    (net (code "62") (name "unconnected-(U1-(TXD1{slash}INT3)PD3-Pad21)") (class "Default")
      (node (ref "U1") (pin "21") (pinfunction "(TXD1/INT3)PD3_21") (pintype "bidirectional+no_connect"))
    )
    (net (code "63") (name "unconnected-(U1-PB6(PCINT6{slash}OC1B{slash}OC4B{slash}ADC)-Pad30)") (class "Default")
      (node (ref "U1") (pin "30") (pinfunction "PB6(PCINT6/OC1B/OC4B/ADC)_30") (pintype "bidirectional+no_connect"))
    )
    (net (code "64") (name "unconnected-(U1-PC6(OC3A{slash}!OC4A!)-Pad31)") (class "Default")
      (node (ref "U1") (pin "31") (pinfunction "PC6(OC3A/!OC4A!)_31") (pintype "bidirectional+no_connect"))
    )
    (net (code "65") (name "unconnected-(U1-PC7(ICP3{slash}CLK0{slash}OC4A)-Pad32)") (class "Default")
      (node (ref "U1") (pin "32") (pinfunction "PC7(ICP3/CLK0/OC4A)_32") (pintype "bidirectional+no_connect"))
    )
    (net (code "66") (name "unconnected-(U1-PD4(ICP1{slash}ADC8)-Pad25)") (class "Default")
      (node (ref "U1") (pin "25") (pinfunction "PD4(ICP1/ADC8)_25") (pintype "bidirectional+no_connect"))
    )
    (net (code "67") (name "unconnected-(U1-PD6(T1{slash}!OC4D!{slash}ADC9)-Pad26)") (class "Default")
      (node (ref "U1") (pin "26") (pinfunction "PD6(T1/!OC4D!/ADC9)_26") (pintype "bidirectional+no_connect"))
    )
    (net (code "68") (name "unconnected-(U1-PD7(T0{slash}OC4D{slash}ADC10)-Pad27)") (class "Default")
      (node (ref "U1") (pin "27") (pinfunction "PD7(T0/OC4D/ADC10)_27") (pintype "bidirectional+no_connect"))
    )
    (net (code "69") (name "unconnected-(U1-PF0(ADC0)-Pad41)") (class "Default")
      (node (ref "U1") (pin "41") (pinfunction "PF0(ADC0)_41") (pintype "bidirectional+no_connect"))
    )
    (net (code "70") (name "unconnected-(U1-PF1(ADC1)-Pad40)") (class "Default")
      (node (ref "U1") (pin "40") (pinfunction "PF1(ADC1)_40") (pintype "bidirectional+no_connect"))
    )
    (net (code "71") (name "unconnected-(U1-PF4(ADC4{slash}TCK)-Pad39)") (class "Default")
      (node (ref "U1") (pin "39") (pinfunction "PF4(ADC4/TCK)_39") (pintype "bidirectional+no_connect"))
    )
    (net (code "72") (name "unconnected-(U1-PF5(ADC5{slash}TMS)-Pad38)") (class "Default")
      (node (ref "U1") (pin "38") (pinfunction "PF5(ADC5/TMS)_38") (pintype "bidirectional+no_connect"))
    )
    (net (code "73") (name "unconnected-(U1-PF6(ADC6{slash}TDO)-Pad37)") (class "Default")
      (node (ref "U1") (pin "37") (pinfunction "PF6(ADC6/TDO)_37") (pintype "bidirectional+no_connect"))
    )
    (net (code "74") (name "unconnected-(U1-PF7(ADC7{slash}TDI)-Pad36)") (class "Default")
      (node (ref "U1") (pin "36") (pinfunction "PF7(ADC7/TDI)_36") (pintype "bidirectional+no_connect"))
    )
    (net (code "75") (name "unconnected-(U2-VREF-Pad5)") (class "Default")
      (node (ref "U2") (pin "5") (pinfunction "VREF_5") (pintype "output+no_connect"))
    )
    (net (code "76") (name "unconnected-(U3-CLKOUT{slash}SOF-Pad3)") (class "Default")
      (node (ref "U3") (pin "3") (pinfunction "CLKOUT/SOF_3") (pintype "output+no_connect"))
    )
    (net (code "77") (name "unconnected-(U3-~{INT}-Pad12)") (class "Default")
      (node (ref "U3") (pin "12") (pinfunction "~{INT}_12") (pintype "output+no_connect"))
    )
    (net (code "78") (name "unconnected-(U3-~{RX0BF}-Pad11)") (class "Default")
      (node (ref "U3") (pin "11") (pinfunction "~{RX0BF}_11") (pintype "output+no_connect"))
    )
    (net (code "79") (name "unconnected-(U3-~{RX1BF}-Pad10)") (class "Default")
      (node (ref "U3") (pin "10") (pinfunction "~{RX1BF}_10") (pintype "output+no_connect"))
    )
    (net (code "80") (name "unconnected-(U3-~{TX0RTS}-Pad4)") (class "Default")
      (node (ref "U3") (pin "4") (pinfunction "~{TX0RTS}_4") (pintype "input+no_connect"))
    )
    (net (code "81") (name "unconnected-(U3-~{TX1RTS}-Pad5)") (class "Default")
      (node (ref "U3") (pin "5") (pinfunction "~{TX1RTS}_5") (pintype "input+no_connect"))
    )
    (net (code "82") (name "unconnected-(U3-~{TX2RTS}-Pad6)") (class "Default")
      (node (ref "U3") (pin "6") (pinfunction "~{TX2RTS}_6") (pintype "input+no_connect"))
    )
    (net (code "83") (name "unconnected-(U4-VREF-Pad5)") (class "Default")
      (node (ref "U4") (pin "5") (pinfunction "VREF_5") (pintype "output+no_connect"))
    )
    (net (code "84") (name "unconnected-(U5-CLKOUT{slash}SOF-Pad3)") (class "Default")
      (node (ref "U5") (pin "3") (pinfunction "CLKOUT/SOF_3") (pintype "output+no_connect"))
    )
    (net (code "85") (name "unconnected-(U5-~{INT}-Pad12)") (class "Default")
      (node (ref "U5") (pin "12") (pinfunction "~{INT}_12") (pintype "output+no_connect"))
    )
    (net (code "86") (name "unconnected-(U5-~{RX0BF}-Pad11)") (class "Default")
      (node (ref "U5") (pin "11") (pinfunction "~{RX0BF}_11") (pintype "output+no_connect"))
    )
    (net (code "87") (name "unconnected-(U5-~{RX1BF}-Pad10)") (class "Default")
      (node (ref "U5") (pin "10") (pinfunction "~{RX1BF}_10") (pintype "output+no_connect"))
    )
    (net (code "88") (name "unconnected-(U5-~{TX0RTS}-Pad4)") (class "Default")
      (node (ref "U5") (pin "4") (pinfunction "~{TX0RTS}_4") (pintype "input+no_connect"))
    )
    (net (code "89") (name "unconnected-(U5-~{TX1RTS}-Pad5)") (class "Default")
      (node (ref "U5") (pin "5") (pinfunction "~{TX1RTS}_5") (pintype "input+no_connect"))
    )
    (net (code "90") (name "unconnected-(U5-~{TX2RTS}-Pad6)") (class "Default")
      (node (ref "U5") (pin "6") (pinfunction "~{TX2RTS}_6") (pintype "input+no_connect"))
    )
  )
)
